# SCH-MAKEY_MAKEY_PTITTEAM_161016.net
KiCad netlist of a schematic drawn in Altium Designer
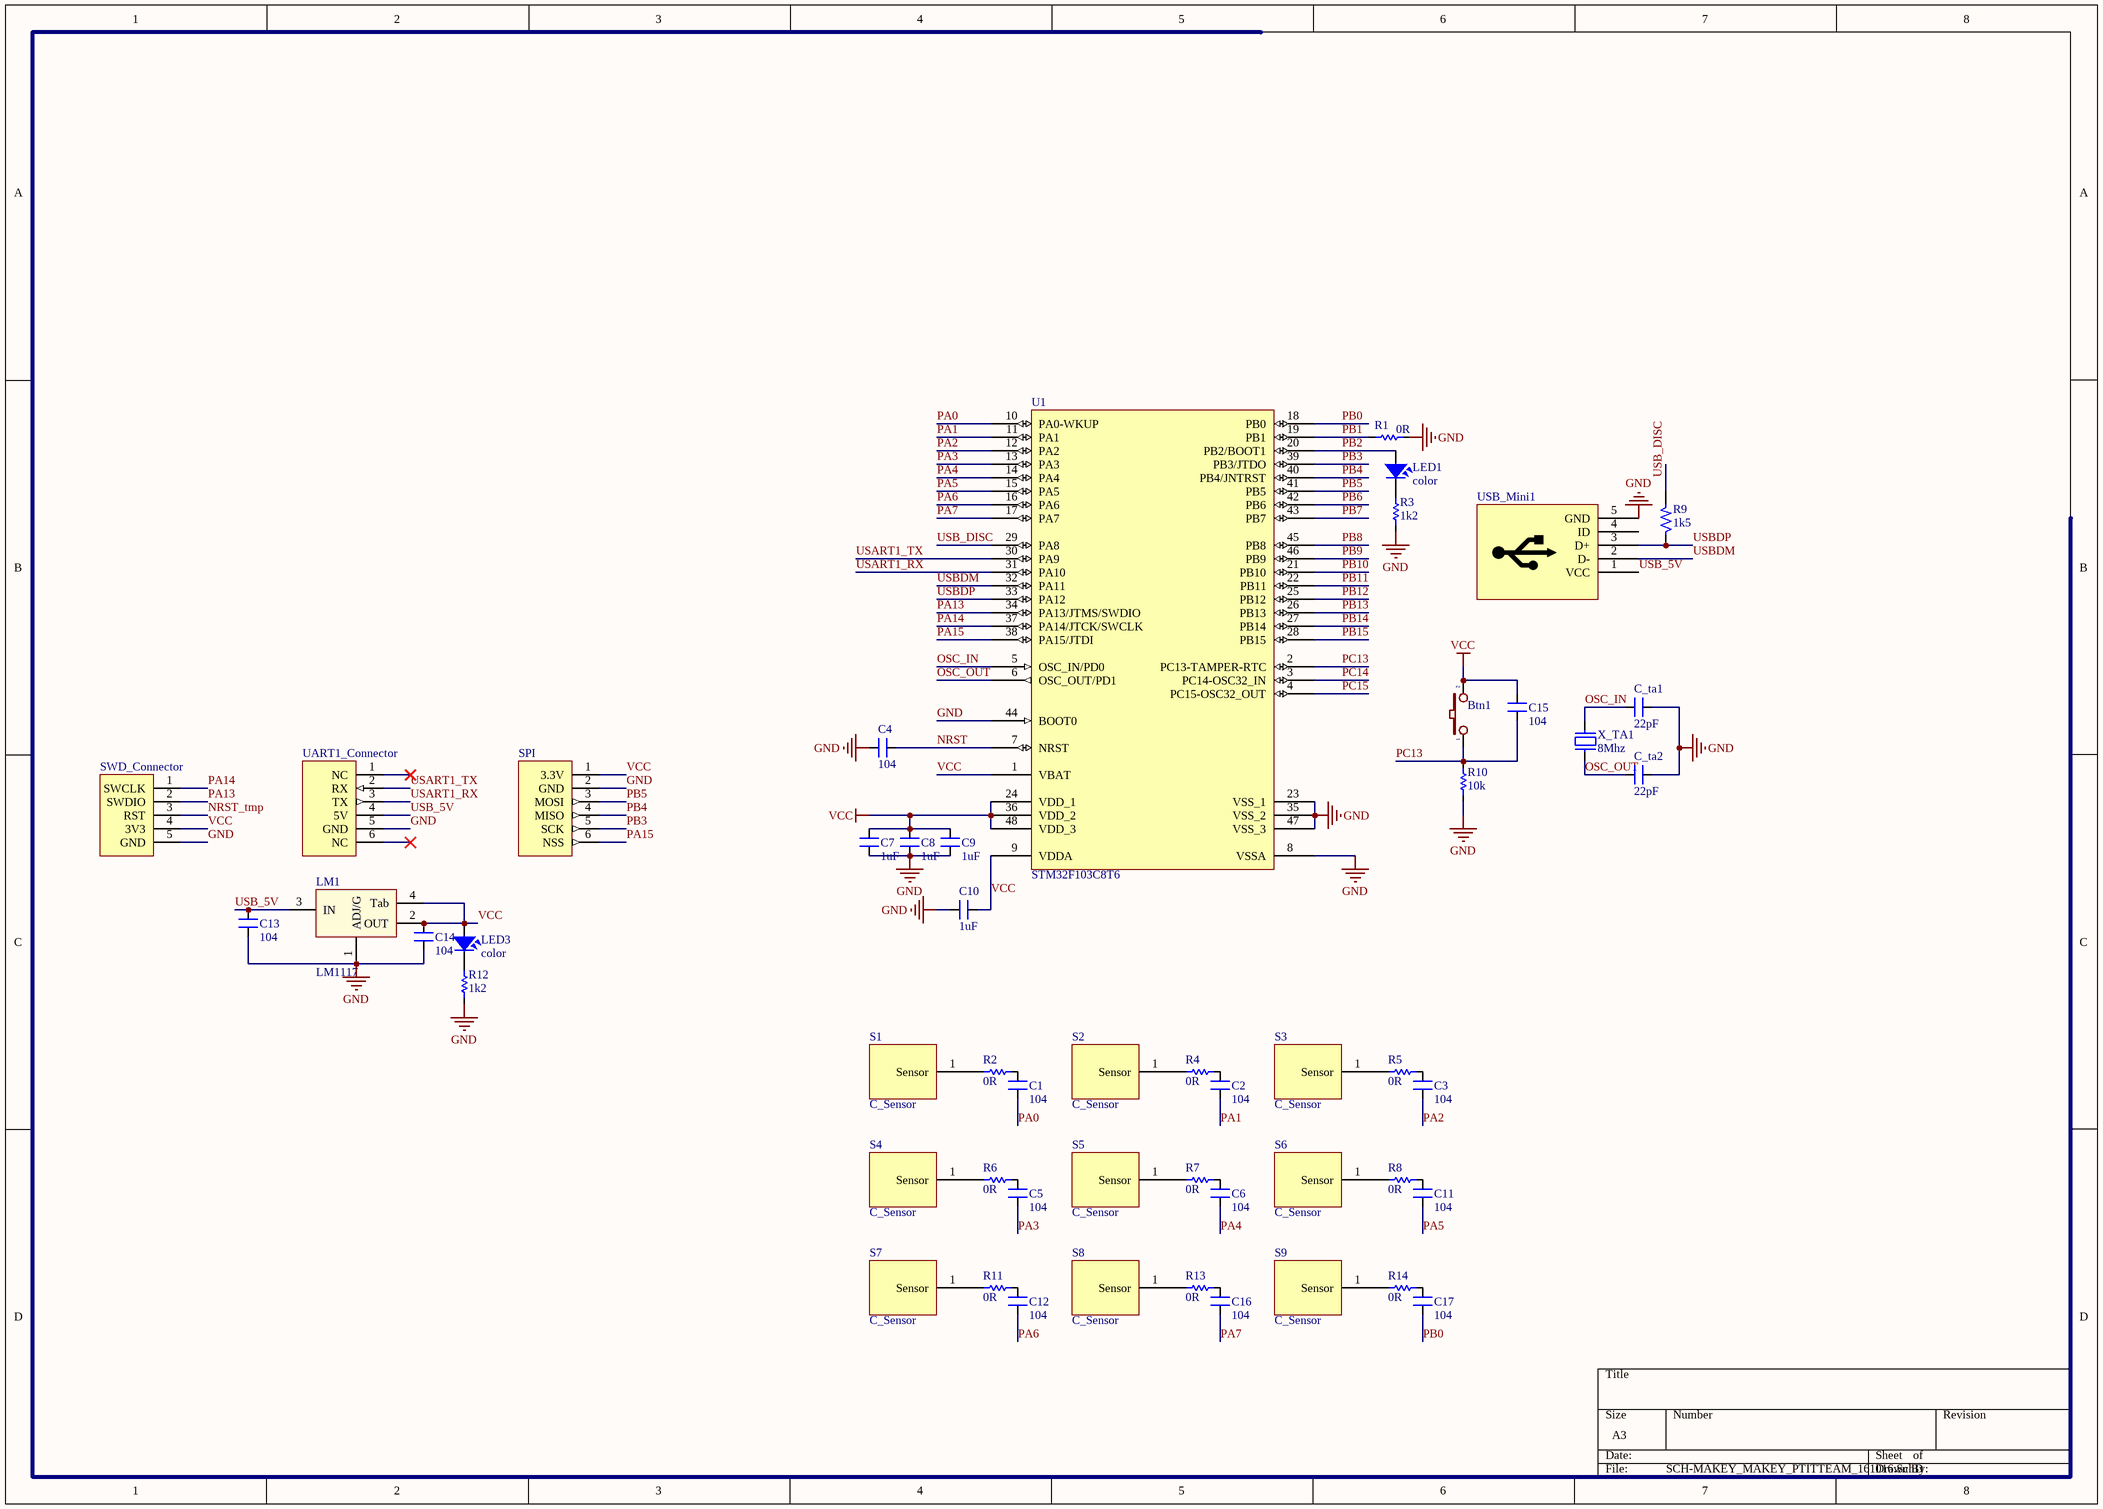
[diagram p0: SCH-MAKEY_MAKEY_PTITTEAM_161016.SchDoc]

(export (version "E")
  (design (tool "Eeschema 10.0.6"))
  (components
    (comp (ref "Btn1")
      (value "Function")
      (footprint "Button_SMD_2pin")
      (description "Switch button 2 pin")
      (libsource (lib "ptit_team_lib") (part "Button_SMD_2pin"))
    )
    (comp (ref "C1")
      (value "104")
      (footprint "CAP-0603")
      (description "Cap SMD")
      (libsource (lib "syhaunguyen") (part "CM"))
    )
    (comp (ref "C2")
      (value "104")
      (footprint "CAP-0603")
      (description "Cap SMD")
      (libsource (lib "syhaunguyen") (part "CM"))
    )
    (comp (ref "C3")
      (value "104")
      (footprint "CAP-0603")
      (description "Cap SMD")
      (libsource (lib "syhaunguyen") (part "CM"))
    )
    (comp (ref "C4")
      (value "104")
      (footprint "CAP-0603")
      (description "Cap SMD")
      (libsource (lib "syhaunguyen") (part "CM"))
    )
    (comp (ref "C5")
      (value "104")
      (footprint "CAP-0603")
      (description "Cap SMD")
      (libsource (lib "syhaunguyen") (part "CM"))
    )
    (comp (ref "C6")
      (value "104")
      (footprint "CAP-0603")
      (description "Cap SMD")
      (libsource (lib "syhaunguyen") (part "CM"))
    )
    (comp (ref "C7")
      (value "1uF")
      (footprint "CAP-0603")
      (description "Cremic For Xtal 1pF => 100pF")
      (libsource (lib "syhaunguyen") (part "CN0"))
    )
    (comp (ref "C8")
      (value "1uF")
      (footprint "CAP-0603")
      (description "Cremic For Xtal 1pF => 100pF")
      (libsource (lib "syhaunguyen") (part "CN0"))
    )
    (comp (ref "C9")
      (value "1uF")
      (footprint "CAP-0603")
      (description "Cap SMD")
      (libsource (lib "syhaunguyen") (part "CM"))
    )
    (comp (ref "C10")
      (value "1uF")
      (footprint "CAP-0603")
      (description "Cap SMD")
      (libsource (lib "syhaunguyen") (part "CM"))
    )
    (comp (ref "C11")
      (value "104")
      (footprint "CAP-0603")
      (description "Cap SMD")
      (libsource (lib "syhaunguyen") (part "CM"))
    )
    (comp (ref "C12")
      (value "104")
      (footprint "CAP-0603")
      (description "Cremic For Xtal 1pF => 100pF")
      (libsource (lib "syhaunguyen") (part "CN0"))
    )
    (comp (ref "C13")
      (value "104")
      (footprint "CAP-0603")
      (description "Cap SMD")
      (libsource (lib "syhaunguyen") (part "CM"))
    )
    (comp (ref "C14")
      (value "104")
      (footprint "CAP-0603")
      (description "Cap SMD")
      (libsource (lib "syhaunguyen") (part "CM"))
    )
    (comp (ref "C15")
      (value "104")
      (footprint "CAP-0603")
      (description "Cap SMD")
      (libsource (lib "syhaunguyen") (part "CM"))
    )
    (comp (ref "C16")
      (value "104")
      (footprint "CAP-0603")
      (description "Cremic For Xtal 1pF => 100pF")
      (libsource (lib "syhaunguyen") (part "CN0"))
    )
    (comp (ref "C17")
      (value "104")
      (footprint "CAP-0603")
      (description "Cremic For Xtal 1pF => 100pF")
      (libsource (lib "syhaunguyen") (part "CN0"))
    )
    (comp (ref "C_ta1")
      (value "22pF")
      (footprint "CAP-0603")
      (description "Cremic For Xtal 1pF => 100pF")
      (libsource (lib "syhaunguyen") (part "CN0"))
    )
    (comp (ref "C_ta2")
      (value "22pF")
      (footprint "CAP-0603")
      (description "Cremic For Xtal 1pF => 100pF")
      (libsource (lib "syhaunguyen") (part "CN0"))
    )
    (comp (ref "LED1")
      (value "color")
      (footprint "LED-0805")
      (description "Led smd")
      (libsource (lib "ptit_team_lib") (part "Led_SMD"))
    )
    (comp (ref "LED3")
      (value "color")
      (footprint "LED-0805")
      (description "Led smd")
      (libsource (lib "ptit_team_lib") (part "Led_SMD"))
    )
    (comp (ref "LM1")
      (value "LM1117")
      (footprint "SOT223-4N")
      (description "3v3")
      (libsource (lib "syhaunguyen") (part "LM1117"))
    )
    (comp (ref "R1")
      (value "0R")
      (footprint "RES-0603")
      (description "Resistor smd 0603 type")
      (libsource (lib "ptit_team_lib") (part "Res_SMD_0603"))
    )
    (comp (ref "R2")
      (value "0R")
      (footprint "RES-0603")
      (description "Resistor smd 0603 type")
      (libsource (lib "ptit_team_lib") (part "Res_SMD_0603"))
    )
    (comp (ref "R3")
      (value "1k2")
      (footprint "RES-0603")
      (description "Resistor smd 0603 type")
      (libsource (lib "ptit_team_lib") (part "Res_SMD_0603"))
    )
    (comp (ref "R4")
      (value "0R")
      (footprint "RES-0603")
      (description "Resistor smd 0603 type")
      (libsource (lib "ptit_team_lib") (part "Res_SMD_0603"))
    )
    (comp (ref "R5")
      (value "0R")
      (footprint "RES-0603")
      (description "Resistor smd 0603 type")
      (libsource (lib "ptit_team_lib") (part "Res_SMD_0603"))
    )
    (comp (ref "R6")
      (value "0R")
      (footprint "RES-0603")
      (description "Resistor smd 0603 type")
      (libsource (lib "ptit_team_lib") (part "Res_SMD_0603"))
    )
    (comp (ref "R7")
      (value "0R")
      (footprint "RES-0603")
      (description "Resistor smd 0603 type")
      (libsource (lib "ptit_team_lib") (part "Res_SMD_0603"))
    )
    (comp (ref "R8")
      (value "0R")
      (footprint "RES-0603")
      (description "Resistor smd 0603 type")
      (libsource (lib "ptit_team_lib") (part "Res_SMD_0603"))
    )
    (comp (ref "R9")
      (value "1k5")
      (footprint "RES-0603")
      (description "Resistor 1/4W")
      (libsource (lib "syhaunguyen") (part "R"))
    )
    (comp (ref "R10")
      (value "10k")
      (footprint "RES-0603")
      (description "Resistor smd 0603 type")
      (libsource (lib "ptit_team_lib") (part "Res_SMD_0603"))
    )
    (comp (ref "R11")
      (value "0R")
      (footprint "RES-0603")
      (description "Resistor smd 0603 type")
      (libsource (lib "ptit_team_lib") (part "Res_SMD_0603"))
    )
    (comp (ref "R12")
      (value "1k2")
      (footprint "RES-0603")
      (description "Resistor smd 0603 type")
      (libsource (lib "ptit_team_lib") (part "Res_SMD_0603"))
    )
    (comp (ref "R13")
      (value "0R")
      (footprint "RES-0603")
      (description "Resistor smd 0603 type")
      (libsource (lib "ptit_team_lib") (part "Res_SMD_0603"))
    )
    (comp (ref "R14")
      (value "0R")
      (footprint "RES-0603")
      (description "Resistor smd 0603 type")
      (libsource (lib "ptit_team_lib") (part "Res_SMD_0603"))
    )
    (comp (ref "S1") (value "C_Sensor") (footprint "SOP2") (libsource (lib "C_sensor") (part "C_Sensor")))
    (comp (ref "S2") (value "C_Sensor") (footprint "SOP2") (libsource (lib "C_sensor") (part "C_Sensor")))
    (comp (ref "S3") (value "C_Sensor") (footprint "SOP2") (libsource (lib "C_sensor") (part "C_Sensor")))
    (comp (ref "S4") (value "C_Sensor") (footprint "SOP2") (libsource (lib "C_sensor") (part "C_Sensor")))
    (comp (ref "S5") (value "C_Sensor") (footprint "SOP2") (libsource (lib "C_sensor") (part "C_Sensor")))
    (comp (ref "S6") (value "C_Sensor") (footprint "SOP2") (libsource (lib "C_sensor") (part "C_Sensor")))
    (comp (ref "S7") (value "C_Sensor") (footprint "SOP2") (libsource (lib "C_sensor") (part "C_Sensor")))
    (comp (ref "S8") (value "C_Sensor") (footprint "SOP2") (libsource (lib "C_sensor") (part "C_Sensor")))
    (comp (ref "S9") (value "C_Sensor") (footprint "SOP2") (libsource (lib "C_sensor") (part "C_Sensor")))
    (comp (ref "SPI") (value "~") (footprint "JP6") (libsource (lib "ptit_team_lib") (part "SPI_Connector")))
    (comp (ref "SWD_Connector")
      (value "~")
      (footprint "JP_5")
      (libsource (lib "ptit_team_lib") (part "Load_Program"))
    )
    (comp (ref "U1")
      (value "STM32F103C8T6")
      (footprint "LQFP48_N")
      (description "STM32 ARM-based 32-bit MCU with 64 Kbytes Flash, 48-pin LQFP, Industrial Temperature")
      (fields (field (name "PUBLISHER") "Altium Limited"))
      (libsource (lib "STM32F103C8T6") (part "STM32F103C8T6"))
    )
    (comp (ref "UART1_Connector")
      (value "Connector")
      (footprint "JP6")
      (description "Connector to USB2Com module")
      (libsource (lib "ptit_team_lib") (part "USB2Com_Conn"))
    )
    (comp (ref "USB_Mini1") (value "~") (footprint "Micro_USB") (libsource (lib "ARM") (part "USB_M")))
    (comp (ref "X_TA1")
      (value "8Mhz")
      (footprint "XT2")
      (description "Crystal For all Crystal 2pin.")
      (libsource (lib "syhaunguyen") (part "XT2"))
    )
  )
  (nets
    (net (code "1") (name "/NRST") (class "Default")
      (node (ref "C4") (pin "1") (pinfunction "1_1") (pintype "passive"))
      (node (ref "U1") (pin "7") (pinfunction "NRST_7") (pintype "bidirectional"))
    )
    (net (code "2") (name "/NRST_tmp") (class "Default")
      (node (ref "SWD_Connector") (pin "3") (pinfunction "RST_3") (pintype "open_emitter"))
    )
    (net (code "3") (name "/OSC_IN") (class "Default")
      (node (ref "C_ta1") (pin "1") (pinfunction "1_1") (pintype "passive"))
      (node (ref "U1") (pin "5") (pinfunction "OSC_IN/PD0_5") (pintype "input"))
      (node (ref "X_TA1") (pin "2") (pinfunction "2_2") (pintype "passive"))
    )
    (net (code "4") (name "/OSC_OUT") (class "Default")
      (node (ref "C_ta2") (pin "1") (pinfunction "1_1") (pintype "passive"))
      (node (ref "U1") (pin "6") (pinfunction "OSC_OUT/PD1_6") (pintype "output"))
      (node (ref "X_TA1") (pin "1") (pinfunction "1_1") (pintype "passive"))
    )
    (net (code "5") (name "/PA0") (class "Default")
      (node (ref "C1") (pin "1") (pinfunction "1_1") (pintype "passive"))
      (node (ref "U1") (pin "10") (pinfunction "PA0-WKUP_10") (pintype "bidirectional"))
    )
    (net (code "6") (name "/PA1") (class "Default")
      (node (ref "C2") (pin "1") (pinfunction "1_1") (pintype "passive"))
      (node (ref "U1") (pin "11") (pinfunction "PA1_11") (pintype "bidirectional"))
    )
    (net (code "7") (name "/PA2") (class "Default")
      (node (ref "C3") (pin "1") (pinfunction "1_1") (pintype "passive"))
      (node (ref "U1") (pin "12") (pinfunction "PA2_12") (pintype "bidirectional"))
    )
    (net (code "8") (name "/PA3") (class "Default")
      (node (ref "C5") (pin "1") (pinfunction "1_1") (pintype "passive"))
      (node (ref "U1") (pin "13") (pinfunction "PA3_13") (pintype "bidirectional"))
    )
    (net (code "9") (name "/PA4") (class "Default")
      (node (ref "C6") (pin "1") (pinfunction "1_1") (pintype "passive"))
      (node (ref "U1") (pin "14") (pinfunction "PA4_14") (pintype "bidirectional"))
    )
    (net (code "10") (name "/PA5") (class "Default")
      (node (ref "C11") (pin "1") (pinfunction "1_1") (pintype "passive"))
      (node (ref "U1") (pin "15") (pinfunction "PA5_15") (pintype "bidirectional"))
    )
    (net (code "11") (name "/PA6") (class "Default")
      (node (ref "C12") (pin "1") (pinfunction "1_1") (pintype "passive"))
      (node (ref "U1") (pin "16") (pinfunction "PA6_16") (pintype "bidirectional"))
    )
    (net (code "12") (name "/PA7") (class "Default")
      (node (ref "C16") (pin "1") (pinfunction "1_1") (pintype "passive"))
      (node (ref "U1") (pin "17") (pinfunction "PA7_17") (pintype "bidirectional"))
    )
    (net (code "13") (name "/PA13") (class "Default")
      (node (ref "SWD_Connector") (pin "2") (pinfunction "SWDIO_2") (pintype "open_emitter"))
      (node (ref "U1") (pin "34") (pinfunction "PA13/JTMS/SWDIO_34") (pintype "bidirectional"))
    )
    (net (code "14") (name "/PA14") (class "Default")
      (node (ref "SWD_Connector") (pin "1") (pinfunction "SWCLK_1") (pintype "open_emitter"))
      (node (ref "U1") (pin "37") (pinfunction "PA14/JTCK/SWCLK_37") (pintype "bidirectional"))
    )
    (net (code "15") (name "/PA15") (class "Default")
      (node (ref "SPI") (pin "6") (pinfunction "NSS_6") (pintype "output"))
      (node (ref "U1") (pin "38") (pinfunction "PA15/JTDI_38") (pintype "bidirectional"))
    )
    (net (code "16") (name "/PB0") (class "Default")
      (node (ref "C17") (pin "1") (pinfunction "1_1") (pintype "passive"))
      (node (ref "U1") (pin "18") (pinfunction "PB0_18") (pintype "bidirectional"))
    )
    (net (code "17") (name "/PB1") (class "Default")
      (node (ref "R1") (pin "2") (pinfunction "2_2") (pintype "passive"))
      (node (ref "U1") (pin "19") (pinfunction "PB1_19") (pintype "bidirectional"))
    )
    (net (code "18") (name "/PB2") (class "Default")
      (node (ref "LED1") (pin "1") (pinfunction "1_1") (pintype "passive"))
      (node (ref "U1") (pin "20") (pinfunction "PB2/BOOT1_20") (pintype "bidirectional"))
    )
    (net (code "19") (name "/PB3") (class "Default")
      (node (ref "SPI") (pin "5") (pinfunction "SCK_5") (pintype "output"))
      (node (ref "U1") (pin "39") (pinfunction "PB3/JTDO_39") (pintype "bidirectional"))
    )
    (net (code "20") (name "/PB4") (class "Default")
      (node (ref "SPI") (pin "4") (pinfunction "MISO_4") (pintype "output"))
      (node (ref "U1") (pin "40") (pinfunction "PB4/JNTRST_40") (pintype "bidirectional"))
    )
    (net (code "21") (name "/PB5") (class "Default")
      (node (ref "SPI") (pin "3") (pinfunction "MOSI_3") (pintype "output"))
      (node (ref "U1") (pin "41") (pinfunction "PB5_41") (pintype "bidirectional"))
    )
    (net (code "22") (name "/PB6") (class "Default")
      (node (ref "U1") (pin "42") (pinfunction "PB6_42") (pintype "bidirectional"))
    )
    (net (code "23") (name "/PB7") (class "Default")
      (node (ref "U1") (pin "43") (pinfunction "PB7_43") (pintype "bidirectional"))
    )
    (net (code "24") (name "/PB8") (class "Default")
      (node (ref "U1") (pin "45") (pinfunction "PB8_45") (pintype "bidirectional"))
    )
    (net (code "25") (name "/PB9") (class "Default")
      (node (ref "U1") (pin "46") (pinfunction "PB9_46") (pintype "bidirectional"))
    )
    (net (code "26") (name "/PB10") (class "Default")
      (node (ref "U1") (pin "21") (pinfunction "PB10_21") (pintype "bidirectional"))
    )
    (net (code "27") (name "/PB11") (class "Default")
      (node (ref "U1") (pin "22") (pinfunction "PB11_22") (pintype "bidirectional"))
    )
    (net (code "28") (name "/PB12") (class "Default")
      (node (ref "U1") (pin "25") (pinfunction "PB12_25") (pintype "bidirectional"))
    )
    (net (code "29") (name "/PB13") (class "Default")
      (node (ref "U1") (pin "26") (pinfunction "PB13_26") (pintype "bidirectional"))
    )
    (net (code "30") (name "/PB14") (class "Default")
      (node (ref "U1") (pin "27") (pinfunction "PB14_27") (pintype "bidirectional"))
    )
    (net (code "31") (name "/PB15") (class "Default")
      (node (ref "U1") (pin "28") (pinfunction "PB15_28") (pintype "bidirectional"))
    )
    (net (code "32") (name "/PC13") (class "Default")
      (node (ref "Btn1") (pin "1") (pinfunction "1_1") (pintype "passive"))
      (node (ref "C15") (pin "1") (pinfunction "1_1") (pintype "passive"))
      (node (ref "R10") (pin "2") (pinfunction "2_2") (pintype "passive"))
      (node (ref "U1") (pin "2") (pinfunction "PC13-TAMPER-RTC_2") (pintype "bidirectional"))
    )
    (net (code "33") (name "/PC14") (class "Default")
      (node (ref "U1") (pin "3") (pinfunction "PC14-OSC32_IN_3") (pintype "bidirectional"))
    )
    (net (code "34") (name "/PC15") (class "Default")
      (node (ref "U1") (pin "4") (pinfunction "PC15-OSC32_OUT_4") (pintype "bidirectional"))
    )
    (net (code "35") (name "/USART1_RX") (class "Default")
      (node (ref "U1") (pin "31") (pinfunction "PA10_31") (pintype "bidirectional"))
      (node (ref "UART1_Connector") (pin "3") (pinfunction "TX_3") (pintype "output"))
    )
    (net (code "36") (name "/USART1_TX") (class "Default")
      (node (ref "U1") (pin "30") (pinfunction "PA9_30") (pintype "bidirectional"))
      (node (ref "UART1_Connector") (pin "2") (pinfunction "RX_2") (pintype "input"))
    )
    (net (code "37") (name "/USBDM") (class "Default")
      (node (ref "U1") (pin "32") (pinfunction "PA11_32") (pintype "bidirectional"))
      (node (ref "USB_Mini1") (pin "2") (pinfunction "D-_2") (pintype "passive"))
    )
    (net (code "38") (name "/USBDP") (class "Default")
      (node (ref "R9") (pin "1") (pinfunction "1_1") (pintype "passive"))
      (node (ref "U1") (pin "33") (pinfunction "PA12_33") (pintype "bidirectional"))
      (node (ref "USB_Mini1") (pin "3") (pinfunction "D+_3") (pintype "passive"))
    )
    (net (code "39") (name "/USB_5V") (class "Default")
      (node (ref "C13") (pin "2") (pinfunction "2_2") (pintype "passive"))
      (node (ref "LM1") (pin "3") (pinfunction "IN_3") (pintype "passive"))
      (node (ref "UART1_Connector") (pin "4") (pinfunction "5V_4") (pintype "power_in"))
      (node (ref "USB_Mini1") (pin "1") (pinfunction "VCC_1") (pintype "passive"))
    )
    (net (code "40") (name "/USB_DISC") (class "Default")
      (node (ref "R9") (pin "2") (pinfunction "2_2") (pintype "passive"))
      (node (ref "U1") (pin "29") (pinfunction "PA8_29") (pintype "bidirectional"))
    )
    (net (code "41") (name "GND") (class "Default")
      (node (ref "C10") (pin "2") (pinfunction "2_2") (pintype "passive"))
      (node (ref "C13") (pin "1") (pinfunction "1_1") (pintype "passive"))
      (node (ref "C14") (pin "1") (pinfunction "1_1") (pintype "passive"))
      (node (ref "C4") (pin "2") (pinfunction "2_2") (pintype "passive"))
      (node (ref "C7") (pin "1") (pinfunction "1_1") (pintype "passive"))
      (node (ref "C8") (pin "2") (pinfunction "2_2") (pintype "passive"))
      (node (ref "C9") (pin "1") (pinfunction "1_1") (pintype "passive"))
      (node (ref "C_ta1") (pin "2") (pinfunction "2_2") (pintype "passive"))
      (node (ref "C_ta2") (pin "2") (pinfunction "2_2") (pintype "passive"))
      (node (ref "LM1") (pin "1") (pinfunction "ADJ/G_1") (pintype "passive"))
      (node (ref "R1") (pin "1") (pinfunction "1_1") (pintype "passive"))
      (node (ref "R10") (pin "1") (pinfunction "1_1") (pintype "passive"))
      (node (ref "R12") (pin "1") (pinfunction "1_1") (pintype "passive"))
      (node (ref "R3") (pin "1") (pinfunction "1_1") (pintype "passive"))
      (node (ref "SPI") (pin "2") (pinfunction "GND_2") (pintype "power_in"))
      (node (ref "SWD_Connector") (pin "5") (pinfunction "GND_5") (pintype "power_in"))
      (node (ref "U1") (pin "23") (pinfunction "VSS_1_23") (pintype "power_in"))
      (node (ref "U1") (pin "35") (pinfunction "VSS_2_35") (pintype "power_in"))
      (node (ref "U1") (pin "44") (pinfunction "BOOT0_44") (pintype "input"))
      (node (ref "U1") (pin "47") (pinfunction "VSS_3_47") (pintype "power_in"))
      (node (ref "U1") (pin "8") (pinfunction "VSSA_8") (pintype "power_in"))
      (node (ref "UART1_Connector") (pin "5") (pinfunction "GND_5") (pintype "power_in"))
      (node (ref "USB_Mini1") (pin "5") (pinfunction "GND_5") (pintype "passive"))
    )
    (net (code "42") (name "Net-(C1-Pad2)") (class "Default")
      (node (ref "C1") (pin "2") (pinfunction "2_2") (pintype "passive"))
      (node (ref "R2") (pin "1") (pinfunction "1_1") (pintype "passive"))
    )
    (net (code "43") (name "Net-(C2-Pad2)") (class "Default")
      (node (ref "C2") (pin "2") (pinfunction "2_2") (pintype "passive"))
      (node (ref "R4") (pin "1") (pinfunction "1_1") (pintype "passive"))
    )
    (net (code "44") (name "Net-(C3-Pad2)") (class "Default")
      (node (ref "C3") (pin "2") (pinfunction "2_2") (pintype "passive"))
      (node (ref "R5") (pin "1") (pinfunction "1_1") (pintype "passive"))
    )
    (net (code "45") (name "Net-(C5-Pad2)") (class "Default")
      (node (ref "C5") (pin "2") (pinfunction "2_2") (pintype "passive"))
      (node (ref "R6") (pin "1") (pinfunction "1_1") (pintype "passive"))
    )
    (net (code "46") (name "Net-(C6-Pad2)") (class "Default")
      (node (ref "C6") (pin "2") (pinfunction "2_2") (pintype "passive"))
      (node (ref "R7") (pin "1") (pinfunction "1_1") (pintype "passive"))
    )
    (net (code "47") (name "Net-(C11-Pad2)") (class "Default")
      (node (ref "C11") (pin "2") (pinfunction "2_2") (pintype "passive"))
      (node (ref "R8") (pin "1") (pinfunction "1_1") (pintype "passive"))
    )
    (net (code "48") (name "Net-(C12-Pad2)") (class "Default")
      (node (ref "C12") (pin "2") (pinfunction "2_2") (pintype "passive"))
      (node (ref "R11") (pin "1") (pinfunction "1_1") (pintype "passive"))
    )
    (net (code "49") (name "Net-(C16-Pad2)") (class "Default")
      (node (ref "C16") (pin "2") (pinfunction "2_2") (pintype "passive"))
      (node (ref "R13") (pin "1") (pinfunction "1_1") (pintype "passive"))
    )
    (net (code "50") (name "Net-(C17-Pad2)") (class "Default")
      (node (ref "C17") (pin "2") (pinfunction "2_2") (pintype "passive"))
      (node (ref "R14") (pin "1") (pinfunction "1_1") (pintype "passive"))
    )
    (net (code "51") (name "Net-(LED1-Pad2)") (class "Default")
      (node (ref "LED1") (pin "2") (pinfunction "2_2") (pintype "passive"))
      (node (ref "R3") (pin "2") (pinfunction "2_2") (pintype "passive"))
    )
    (net (code "52") (name "Net-(LED3-Pad2)") (class "Default")
      (node (ref "LED3") (pin "2") (pinfunction "2_2") (pintype "passive"))
      (node (ref "R12") (pin "2") (pinfunction "2_2") (pintype "passive"))
    )
    (net (code "53") (name "Net-(S1-Sensor)") (class "Default")
      (node (ref "R2") (pin "2") (pinfunction "2_2") (pintype "passive"))
      (node (ref "S1") (pin "1") (pinfunction "Sensor_1") (pintype "passive"))
    )
    (net (code "54") (name "Net-(S2-Sensor)") (class "Default")
      (node (ref "R4") (pin "2") (pinfunction "2_2") (pintype "passive"))
      (node (ref "S2") (pin "1") (pinfunction "Sensor_1") (pintype "passive"))
    )
    (net (code "55") (name "Net-(S3-Sensor)") (class "Default")
      (node (ref "R5") (pin "2") (pinfunction "2_2") (pintype "passive"))
      (node (ref "S3") (pin "1") (pinfunction "Sensor_1") (pintype "passive"))
    )
    (net (code "56") (name "Net-(S4-Sensor)") (class "Default")
      (node (ref "R6") (pin "2") (pinfunction "2_2") (pintype "passive"))
      (node (ref "S4") (pin "1") (pinfunction "Sensor_1") (pintype "passive"))
    )
    (net (code "57") (name "Net-(S5-Sensor)") (class "Default")
      (node (ref "R7") (pin "2") (pinfunction "2_2") (pintype "passive"))
      (node (ref "S5") (pin "1") (pinfunction "Sensor_1") (pintype "passive"))
    )
    (net (code "58") (name "Net-(S6-Sensor)") (class "Default")
      (node (ref "R8") (pin "2") (pinfunction "2_2") (pintype "passive"))
      (node (ref "S6") (pin "1") (pinfunction "Sensor_1") (pintype "passive"))
    )
    (net (code "59") (name "Net-(S7-Sensor)") (class "Default")
      (node (ref "R11") (pin "2") (pinfunction "2_2") (pintype "passive"))
      (node (ref "S7") (pin "1") (pinfunction "Sensor_1") (pintype "passive"))
    )
    (net (code "60") (name "Net-(S8-Sensor)") (class "Default")
      (node (ref "R13") (pin "2") (pinfunction "2_2") (pintype "passive"))
      (node (ref "S8") (pin "1") (pinfunction "Sensor_1") (pintype "passive"))
    )
    (net (code "61") (name "Net-(S9-Sensor)") (class "Default")
      (node (ref "R14") (pin "2") (pinfunction "2_2") (pintype "passive"))
      (node (ref "S9") (pin "1") (pinfunction "Sensor_1") (pintype "passive"))
    )
    (net (code "62") (name "VCC") (class "Default")
      (node (ref "Btn1") (pin "2") (pinfunction "2_2") (pintype "passive"))
      (node (ref "C10") (pin "1") (pinfunction "1_1") (pintype "passive"))
      (node (ref "C14") (pin "2") (pinfunction "2_2") (pintype "passive"))
      (node (ref "C15") (pin "2") (pinfunction "2_2") (pintype "passive"))
      (node (ref "C7") (pin "2") (pinfunction "2_2") (pintype "passive"))
      (node (ref "C8") (pin "1") (pinfunction "1_1") (pintype "passive"))
      (node (ref "C9") (pin "2") (pinfunction "2_2") (pintype "passive"))
      (node (ref "LED3") (pin "1") (pinfunction "1_1") (pintype "passive"))
      (node (ref "LM1") (pin "2") (pinfunction "OUT_2") (pintype "passive"))
      (node (ref "LM1") (pin "4") (pinfunction "Tab_4") (pintype "passive"))
      (node (ref "SPI") (pin "1") (pinfunction "3.3V_1") (pintype "open_emitter"))
      (node (ref "SWD_Connector") (pin "4") (pinfunction "3V3_4") (pintype "power_in"))
      (node (ref "U1") (pin "1") (pinfunction "VBAT_1") (pintype "power_in"))
      (node (ref "U1") (pin "24") (pinfunction "VDD_1_24") (pintype "power_in"))
      (node (ref "U1") (pin "36") (pinfunction "VDD_2_36") (pintype "power_in"))
      (node (ref "U1") (pin "48") (pinfunction "VDD_3_48") (pintype "power_in"))
      (node (ref "U1") (pin "9") (pinfunction "VDDA_9") (pintype "power_in"))
    )
    (net (code "63") (name "unconnected-(UART1_Connector-NC-Pad1)") (class "Default")
      (node (ref "UART1_Connector") (pin "1") (pinfunction "NC_1") (pintype "passive+no_connect"))
    )
    (net (code "64") (name "unconnected-(UART1_Connector-NC-Pad6)") (class "Default")
      (node (ref "UART1_Connector") (pin "6") (pinfunction "NC_6") (pintype "passive+no_connect"))
    )
    (net (code "65") (name "unconnected-(USB_Mini1-ID-Pad4)") (class "Default")
      (node (ref "USB_Mini1") (pin "4") (pinfunction "ID_4") (pintype "passive"))
    )
  )
)
